# Encodeurs_Schematic.net
KiCad netlist of a schematic drawn in Altium Designer
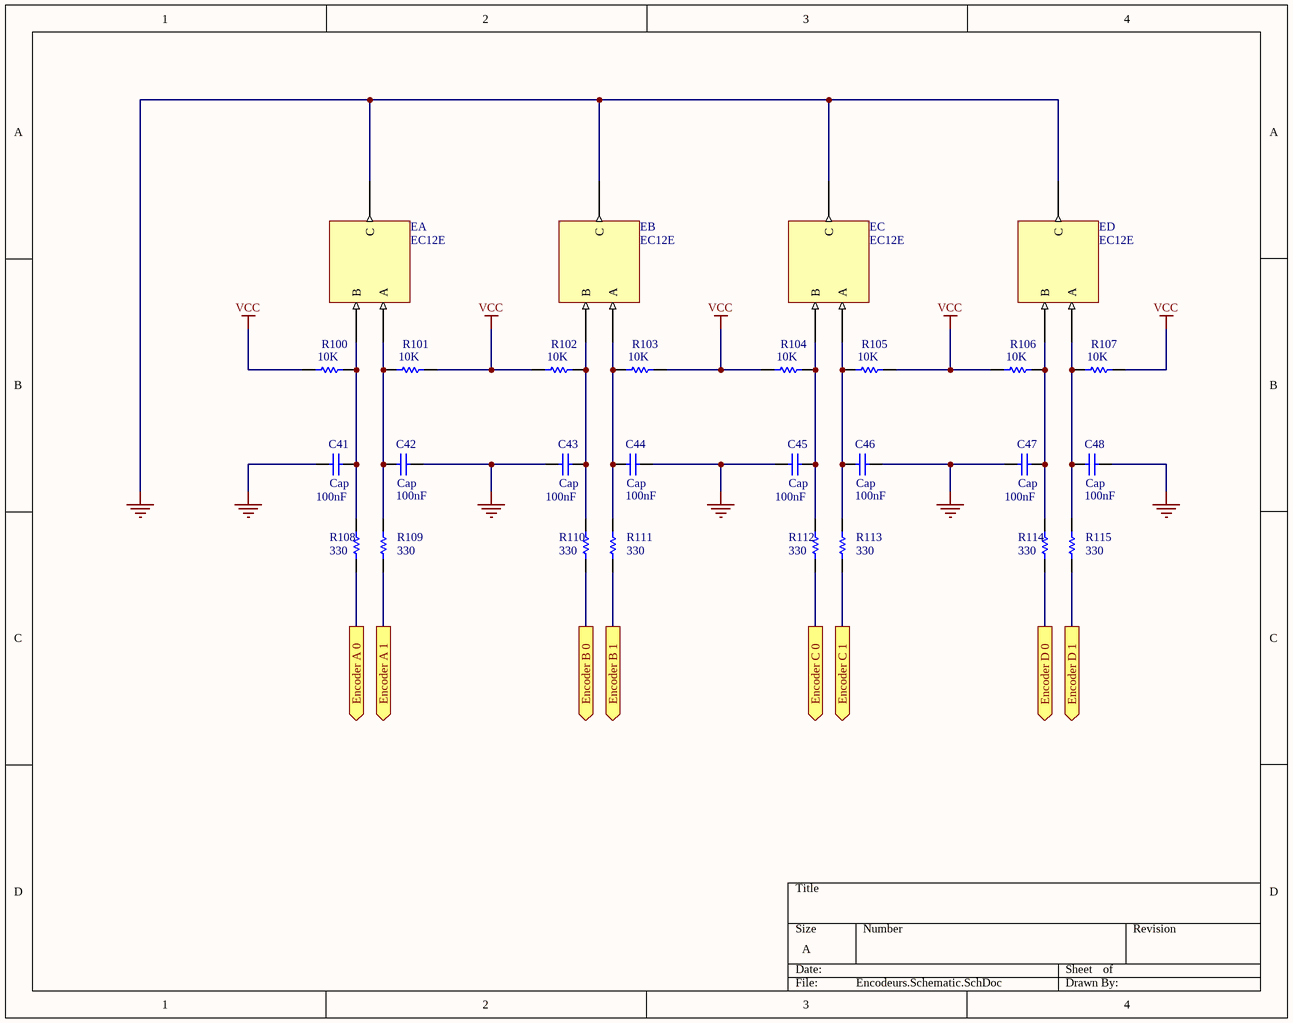
[diagram p0: Encodeurs.Schematic.SchDoc]

(export (version "E")
  (design (tool "Eeschema 10.0.6"))
  (components
    (comp (ref "C41")
      (value "Cap")
      (footprint "CAPC1608N")
      (description "Capacitor")
      (fields (field (name "ALTIUM_VALUE") "100nF") (field (name "PUBLISHER") "Altium Limited"))
      (libsource (lib "Miscellaneous Devices") (part "Cap"))
    )
    (comp (ref "C42")
      (value "Cap")
      (footprint "CAPC1608N")
      (description "Capacitor")
      (fields (field (name "ALTIUM_VALUE") "100nF") (field (name "PUBLISHER") "Altium Limited"))
      (libsource (lib "Miscellaneous Devices") (part "Cap"))
    )
    (comp (ref "C43")
      (value "Cap")
      (footprint "CAPC1608N")
      (description "Capacitor")
      (fields (field (name "ALTIUM_VALUE") "100nF") (field (name "PUBLISHER") "Altium Limited"))
      (libsource (lib "Miscellaneous Devices") (part "Cap"))
    )
    (comp (ref "C44")
      (value "Cap")
      (footprint "CAPC1608N")
      (description "Capacitor")
      (fields (field (name "ALTIUM_VALUE") "100nF") (field (name "PUBLISHER") "Altium Limited"))
      (libsource (lib "Miscellaneous Devices") (part "Cap"))
    )
    (comp (ref "C45")
      (value "Cap")
      (footprint "CAPC1608N")
      (description "Capacitor")
      (fields (field (name "ALTIUM_VALUE") "100nF") (field (name "PUBLISHER") "Altium Limited"))
      (libsource (lib "Miscellaneous Devices") (part "Cap"))
    )
    (comp (ref "C46")
      (value "Cap")
      (footprint "CAPC1608N")
      (description "Capacitor")
      (fields (field (name "ALTIUM_VALUE") "100nF") (field (name "PUBLISHER") "Altium Limited"))
      (libsource (lib "Miscellaneous Devices") (part "Cap"))
    )
    (comp (ref "C47")
      (value "Cap")
      (footprint "CAPC1608N")
      (description "Capacitor")
      (fields (field (name "ALTIUM_VALUE") "100nF") (field (name "PUBLISHER") "Altium Limited"))
      (libsource (lib "Miscellaneous Devices") (part "Cap"))
    )
    (comp (ref "C48")
      (value "Cap")
      (footprint "CAPC1608N")
      (description "Capacitor")
      (fields (field (name "ALTIUM_VALUE") "100nF") (field (name "PUBLISHER") "Altium Limited"))
      (libsource (lib "Miscellaneous Devices") (part "Cap"))
    )
    (comp (ref "EA") (value "EC12E") (libsource (lib "SynthyTwo.Components") (part "EC12E")))
    (comp (ref "EB") (value "EC12E") (libsource (lib "SynthyTwo.Components") (part "EC12E")))
    (comp (ref "EC") (value "EC12E") (libsource (lib "SynthyTwo.Components") (part "EC12E")))
    (comp (ref "ED") (value "EC12E") (libsource (lib "SynthyTwo.Components") (part "EC12E")))
    (comp (ref "R100")
      (value "10K")
      (footprint "AXIAL-0.3")
      (description "Resistor")
      (fields (field (name "PUBLISHER") "Altium Limited"))
      (libsource (lib "Miscellaneous Devices") (part "Res1"))
    )
    (comp (ref "R101")
      (value "10K")
      (footprint "AXIAL-0.3")
      (description "Resistor")
      (fields (field (name "PUBLISHER") "Altium Limited"))
      (libsource (lib "Miscellaneous Devices") (part "Res1"))
    )
    (comp (ref "R102")
      (value "10K")
      (footprint "AXIAL-0.3")
      (description "Resistor")
      (fields (field (name "PUBLISHER") "Altium Limited"))
      (libsource (lib "Miscellaneous Devices") (part "Res1"))
    )
    (comp (ref "R103")
      (value "10K")
      (footprint "AXIAL-0.3")
      (description "Resistor")
      (fields (field (name "PUBLISHER") "Altium Limited"))
      (libsource (lib "Miscellaneous Devices") (part "Res1"))
    )
    (comp (ref "R104")
      (value "10K")
      (footprint "AXIAL-0.3")
      (description "Resistor")
      (fields (field (name "PUBLISHER") "Altium Limited"))
      (libsource (lib "Miscellaneous Devices") (part "Res1"))
    )
    (comp (ref "R105")
      (value "10K")
      (footprint "AXIAL-0.3")
      (description "Resistor")
      (fields (field (name "PUBLISHER") "Altium Limited"))
      (libsource (lib "Miscellaneous Devices") (part "Res1"))
    )
    (comp (ref "R106")
      (value "10K")
      (footprint "AXIAL-0.3")
      (description "Resistor")
      (fields (field (name "PUBLISHER") "Altium Limited"))
      (libsource (lib "Miscellaneous Devices") (part "Res1"))
    )
    (comp (ref "R107")
      (value "10K")
      (footprint "AXIAL-0.3")
      (description "Resistor")
      (fields (field (name "PUBLISHER") "Altium Limited"))
      (libsource (lib "Miscellaneous Devices") (part "Res1"))
    )
    (comp (ref "R108")
      (value "330")
      (footprint "AXIAL-0.3")
      (description "Resistor")
      (fields (field (name "PUBLISHER") "Altium Limited"))
      (libsource (lib "Miscellaneous Devices") (part "Res1"))
    )
    (comp (ref "R109")
      (value "330")
      (footprint "AXIAL-0.3")
      (description "Resistor")
      (fields (field (name "PUBLISHER") "Altium Limited"))
      (libsource (lib "Miscellaneous Devices") (part "Res1"))
    )
    (comp (ref "R110")
      (value "330")
      (footprint "AXIAL-0.3")
      (description "Resistor")
      (fields (field (name "PUBLISHER") "Altium Limited"))
      (libsource (lib "Miscellaneous Devices") (part "Res1"))
    )
    (comp (ref "R111")
      (value "330")
      (footprint "AXIAL-0.3")
      (description "Resistor")
      (fields (field (name "PUBLISHER") "Altium Limited"))
      (libsource (lib "Miscellaneous Devices") (part "Res1"))
    )
    (comp (ref "R112")
      (value "330")
      (footprint "AXIAL-0.3")
      (description "Resistor")
      (fields (field (name "PUBLISHER") "Altium Limited"))
      (libsource (lib "Miscellaneous Devices") (part "Res1"))
    )
    (comp (ref "R113")
      (value "330")
      (footprint "AXIAL-0.3")
      (description "Resistor")
      (fields (field (name "PUBLISHER") "Altium Limited"))
      (libsource (lib "Miscellaneous Devices") (part "Res1"))
    )
    (comp (ref "R114")
      (value "330")
      (footprint "AXIAL-0.3")
      (description "Resistor")
      (fields (field (name "PUBLISHER") "Altium Limited"))
      (libsource (lib "Miscellaneous Devices") (part "Res1"))
    )
    (comp (ref "R115")
      (value "330")
      (footprint "AXIAL-0.3")
      (description "Resistor")
      (fields (field (name "PUBLISHER") "Altium Limited"))
      (libsource (lib "Miscellaneous Devices") (part "Res1"))
    )
  )
  (nets
    (net (code "1") (name "/Encoder A 0") (class "Default")
      (node (ref "R108") (pin "1") (pinfunction "1_1") (pintype "passive"))
    )
    (net (code "2") (name "/Encoder A 1") (class "Default")
      (node (ref "R109") (pin "1") (pinfunction "1_1") (pintype "passive"))
    )
    (net (code "3") (name "/Encoder B 0") (class "Default")
      (node (ref "R110") (pin "1") (pinfunction "1_1") (pintype "passive"))
    )
    (net (code "4") (name "/Encoder B 1") (class "Default")
      (node (ref "R111") (pin "1") (pinfunction "1_1") (pintype "passive"))
    )
    (net (code "5") (name "/Encoder C 0") (class "Default")
      (node (ref "R112") (pin "1") (pinfunction "1_1") (pintype "passive"))
    )
    (net (code "6") (name "/Encoder C 1") (class "Default")
      (node (ref "R113") (pin "1") (pinfunction "1_1") (pintype "passive"))
    )
    (net (code "7") (name "/Encoder D 0") (class "Default")
      (node (ref "R114") (pin "1") (pinfunction "1_1") (pintype "passive"))
    )
    (net (code "8") (name "/Encoder D 1") (class "Default")
      (node (ref "R115") (pin "1") (pinfunction "1_1") (pintype "passive"))
    )
    (net (code "9") (name "GND") (class "Default")
      (node (ref "C41") (pin "1") (pinfunction "1_1") (pintype "passive"))
      (node (ref "C42") (pin "1") (pinfunction "1_1") (pintype "passive"))
      (node (ref "C43") (pin "1") (pinfunction "1_1") (pintype "passive"))
      (node (ref "C44") (pin "1") (pinfunction "1_1") (pintype "passive"))
      (node (ref "C45") (pin "1") (pinfunction "1_1") (pintype "passive"))
      (node (ref "C46") (pin "1") (pinfunction "1_1") (pintype "passive"))
      (node (ref "C47") (pin "1") (pinfunction "1_1") (pintype "passive"))
      (node (ref "C48") (pin "1") (pinfunction "1_1") (pintype "passive"))
      (node (ref "EA") (pin "GND") (pinfunction "C_GND") (pintype "output"))
      (node (ref "EB") (pin "GND") (pinfunction "C_GND") (pintype "output"))
      (node (ref "EC") (pin "GND") (pinfunction "C_GND") (pintype "output"))
      (node (ref "ED") (pin "GND") (pinfunction "C_GND") (pintype "output"))
    )
    (net (code "10") (name "Net-(EA-A)") (class "Default")
      (node (ref "C42") (pin "2") (pinfunction "2_2") (pintype "passive"))
      (node (ref "EA") (pin "Pin_A") (pinfunction "A_Pin_A") (pintype "input"))
      (node (ref "R101") (pin "1") (pinfunction "1_1") (pintype "passive"))
      (node (ref "R109") (pin "2") (pinfunction "2_2") (pintype "passive"))
    )
    (net (code "11") (name "Net-(EA-B)") (class "Default")
      (node (ref "C41") (pin "2") (pinfunction "2_2") (pintype "passive"))
      (node (ref "EA") (pin "Pin_B") (pinfunction "B_Pin_B") (pintype "input"))
      (node (ref "R100") (pin "2") (pinfunction "2_2") (pintype "passive"))
      (node (ref "R108") (pin "2") (pinfunction "2_2") (pintype "passive"))
    )
    (net (code "12") (name "Net-(EB-A)") (class "Default")
      (node (ref "C44") (pin "2") (pinfunction "2_2") (pintype "passive"))
      (node (ref "EB") (pin "Pin_A") (pinfunction "A_Pin_A") (pintype "input"))
      (node (ref "R103") (pin "1") (pinfunction "1_1") (pintype "passive"))
      (node (ref "R111") (pin "2") (pinfunction "2_2") (pintype "passive"))
    )
    (net (code "13") (name "Net-(EB-B)") (class "Default")
      (node (ref "C43") (pin "2") (pinfunction "2_2") (pintype "passive"))
      (node (ref "EB") (pin "Pin_B") (pinfunction "B_Pin_B") (pintype "input"))
      (node (ref "R102") (pin "2") (pinfunction "2_2") (pintype "passive"))
      (node (ref "R110") (pin "2") (pinfunction "2_2") (pintype "passive"))
    )
    (net (code "14") (name "Net-(EC-A)") (class "Default")
      (node (ref "C46") (pin "2") (pinfunction "2_2") (pintype "passive"))
      (node (ref "EC") (pin "Pin_A") (pinfunction "A_Pin_A") (pintype "input"))
      (node (ref "R105") (pin "1") (pinfunction "1_1") (pintype "passive"))
      (node (ref "R113") (pin "2") (pinfunction "2_2") (pintype "passive"))
    )
    (net (code "15") (name "Net-(EC-B)") (class "Default")
      (node (ref "C45") (pin "2") (pinfunction "2_2") (pintype "passive"))
      (node (ref "EC") (pin "Pin_B") (pinfunction "B_Pin_B") (pintype "input"))
      (node (ref "R104") (pin "2") (pinfunction "2_2") (pintype "passive"))
      (node (ref "R112") (pin "2") (pinfunction "2_2") (pintype "passive"))
    )
    (net (code "16") (name "Net-(ED-A)") (class "Default")
      (node (ref "C48") (pin "2") (pinfunction "2_2") (pintype "passive"))
      (node (ref "ED") (pin "Pin_A") (pinfunction "A_Pin_A") (pintype "input"))
      (node (ref "R107") (pin "1") (pinfunction "1_1") (pintype "passive"))
      (node (ref "R115") (pin "2") (pinfunction "2_2") (pintype "passive"))
    )
    (net (code "17") (name "Net-(ED-B)") (class "Default")
      (node (ref "C47") (pin "2") (pinfunction "2_2") (pintype "passive"))
      (node (ref "ED") (pin "Pin_B") (pinfunction "B_Pin_B") (pintype "input"))
      (node (ref "R106") (pin "2") (pinfunction "2_2") (pintype "passive"))
      (node (ref "R114") (pin "2") (pinfunction "2_2") (pintype "passive"))
    )
    (net (code "18") (name "VCC") (class "Default")
      (node (ref "R100") (pin "1") (pinfunction "1_1") (pintype "passive"))
      (node (ref "R101") (pin "2") (pinfunction "2_2") (pintype "passive"))
      (node (ref "R102") (pin "1") (pinfunction "1_1") (pintype "passive"))
      (node (ref "R103") (pin "2") (pinfunction "2_2") (pintype "passive"))
      (node (ref "R104") (pin "1") (pinfunction "1_1") (pintype "passive"))
      (node (ref "R105") (pin "2") (pinfunction "2_2") (pintype "passive"))
      (node (ref "R106") (pin "1") (pinfunction "1_1") (pintype "passive"))
      (node (ref "R107") (pin "2") (pinfunction "2_2") (pintype "passive"))
    )
  )
)
